# Sheet1.net
KiCad netlist of a schematic drawn in Altium Designer
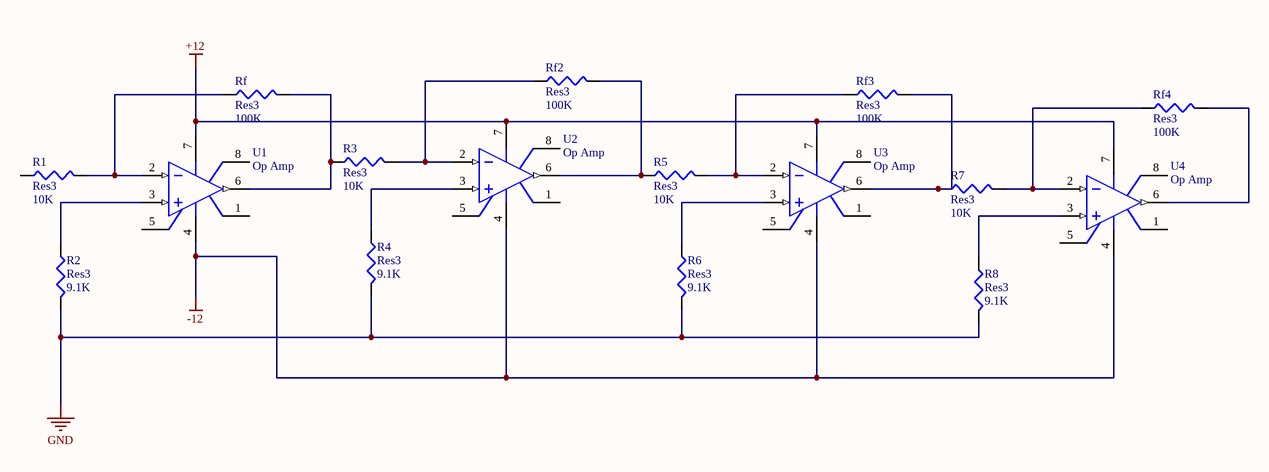
[diagram p0: Sheet1.SchDoc]

(export (version "E")
  (design (tool "Eeschema 10.0.6"))
  (components
    (comp (ref "R1")
      (value "Res3")
      (footprint "J1-0603")
      (description "Resistor")
      (fields (field (name "ALTIUM_VALUE") "10K") (field (name "PUBLISHER") "Altium Limited"))
      (libsource (lib "Miscellaneous Devices") (part "Res3"))
    )
    (comp (ref "R2")
      (value "Res3")
      (footprint "J1-0603")
      (description "Resistor")
      (fields (field (name "ALTIUM_VALUE") "9.1K") (field (name "PUBLISHER") "Altium Limited"))
      (libsource (lib "Miscellaneous Devices") (part "Res3"))
    )
    (comp (ref "R3")
      (value "Res3")
      (footprint "J1-0603")
      (description "Resistor")
      (fields (field (name "ALTIUM_VALUE") "10K") (field (name "PUBLISHER") "Altium Limited"))
      (libsource (lib "Miscellaneous Devices") (part "Res3"))
    )
    (comp (ref "R4")
      (value "Res3")
      (footprint "J1-0603")
      (description "Resistor")
      (fields (field (name "ALTIUM_VALUE") "9.1K") (field (name "PUBLISHER") "Altium Limited"))
      (libsource (lib "Miscellaneous Devices") (part "Res3"))
    )
    (comp (ref "R5")
      (value "Res3")
      (footprint "J1-0603")
      (description "Resistor")
      (fields (field (name "ALTIUM_VALUE") "10K") (field (name "PUBLISHER") "Altium Limited"))
      (libsource (lib "Miscellaneous Devices") (part "Res3"))
    )
    (comp (ref "R6")
      (value "Res3")
      (footprint "J1-0603")
      (description "Resistor")
      (fields (field (name "ALTIUM_VALUE") "9.1K") (field (name "PUBLISHER") "Altium Limited"))
      (libsource (lib "Miscellaneous Devices") (part "Res3"))
    )
    (comp (ref "R7")
      (value "Res3")
      (footprint "J1-0603")
      (description "Resistor")
      (fields (field (name "ALTIUM_VALUE") "10K") (field (name "PUBLISHER") "Altium Limited"))
      (libsource (lib "Miscellaneous Devices") (part "Res3"))
    )
    (comp (ref "R8")
      (value "Res3")
      (footprint "J1-0603")
      (description "Resistor")
      (fields (field (name "ALTIUM_VALUE") "9.1K") (field (name "PUBLISHER") "Altium Limited"))
      (libsource (lib "Miscellaneous Devices") (part "Res3"))
    )
    (comp (ref "Rf")
      (value "Res3")
      (footprint "J1-0603")
      (description "Resistor")
      (fields (field (name "ALTIUM_VALUE") "100K") (field (name "PUBLISHER") "Altium Limited"))
      (libsource (lib "Miscellaneous Devices") (part "Res3"))
    )
    (comp (ref "Rf2")
      (value "Res3")
      (footprint "J1-0603")
      (description "Resistor")
      (fields (field (name "ALTIUM_VALUE") "100K") (field (name "PUBLISHER") "Altium Limited"))
      (libsource (lib "Miscellaneous Devices") (part "Res3"))
    )
    (comp (ref "Rf3")
      (value "Res3")
      (footprint "J1-0603")
      (description "Resistor")
      (fields (field (name "ALTIUM_VALUE") "100K") (field (name "PUBLISHER") "Altium Limited"))
      (libsource (lib "Miscellaneous Devices") (part "Res3"))
    )
    (comp (ref "Rf4")
      (value "Res3")
      (footprint "J1-0603")
      (description "Resistor")
      (fields (field (name "ALTIUM_VALUE") "100K") (field (name "PUBLISHER") "Altium Limited"))
      (libsource (lib "Miscellaneous Devices") (part "Res3"))
    )
    (comp (ref "U1")
      (value "Op Amp")
      (footprint "Miscellaneous Devices:DIP-8")
      (description "FET Operational Amplifier")
      (fields (field (name "PUBLISHER") "Altium Limited"))
      (libsource (lib "Miscellaneous Devices") (part "Op Amp"))
    )
    (comp (ref "U2")
      (value "Op Amp")
      (footprint "Miscellaneous Devices:DIP-8")
      (description "FET Operational Amplifier")
      (fields (field (name "PUBLISHER") "Altium Limited"))
      (libsource (lib "Miscellaneous Devices") (part "Op Amp"))
    )
    (comp (ref "U3")
      (value "Op Amp")
      (footprint "Miscellaneous Devices:DIP-8")
      (description "FET Operational Amplifier")
      (fields (field (name "PUBLISHER") "Altium Limited"))
      (libsource (lib "Miscellaneous Devices") (part "Op Amp"))
    )
    (comp (ref "U4")
      (value "Op Amp")
      (footprint "Miscellaneous Devices:DIP-8")
      (description "FET Operational Amplifier")
      (fields (field (name "PUBLISHER") "Altium Limited"))
      (libsource (lib "Miscellaneous Devices") (part "Op Amp"))
    )
  )
  (nets
    (net (code "1") (name "+12") (class "Default")
      (node (ref "U1") (pin "7") (pinfunction "V+_7") (pintype "power_in"))
      (node (ref "U2") (pin "7") (pinfunction "V+_7") (pintype "power_in"))
      (node (ref "U3") (pin "7") (pinfunction "V+_7") (pintype "power_in"))
      (node (ref "U4") (pin "7") (pinfunction "V+_7") (pintype "power_in"))
    )
    (net (code "2") (name "-12") (class "Default")
      (node (ref "U1") (pin "4") (pinfunction "V-_4") (pintype "power_in"))
      (node (ref "U2") (pin "4") (pinfunction "V-_4") (pintype "power_in"))
      (node (ref "U3") (pin "4") (pinfunction "V-_4") (pintype "power_in"))
      (node (ref "U4") (pin "4") (pinfunction "V-_4") (pintype "power_in"))
    )
    (net (code "3") (name "GND") (class "Default")
      (node (ref "R2") (pin "2") (pinfunction "2_2") (pintype "passive"))
      (node (ref "R4") (pin "2") (pinfunction "2_2") (pintype "passive"))
      (node (ref "R6") (pin "2") (pinfunction "2_2") (pintype "passive"))
      (node (ref "R8") (pin "2") (pinfunction "2_2") (pintype "passive"))
    )
    (net (code "4") (name "Net-(U1-IN+)") (class "Default")
      (node (ref "R2") (pin "1") (pinfunction "1_1") (pintype "passive"))
      (node (ref "U1") (pin "3") (pinfunction "IN+_3") (pintype "input"))
    )
    (net (code "5") (name "Net-(U1-IN-)") (class "Default")
      (node (ref "R1") (pin "2") (pinfunction "2_2") (pintype "passive"))
      (node (ref "Rf") (pin "1") (pinfunction "1_1") (pintype "passive"))
      (node (ref "U1") (pin "2") (pinfunction "IN-_2") (pintype "input"))
    )
    (net (code "6") (name "Net-(U1-OUT)") (class "Default")
      (node (ref "R3") (pin "1") (pinfunction "1_1") (pintype "passive"))
      (node (ref "Rf") (pin "2") (pinfunction "2_2") (pintype "passive"))
      (node (ref "U1") (pin "6") (pinfunction "OUT_6") (pintype "output"))
    )
    (net (code "7") (name "Net-(U2-IN+)") (class "Default")
      (node (ref "R4") (pin "1") (pinfunction "1_1") (pintype "passive"))
      (node (ref "U2") (pin "3") (pinfunction "IN+_3") (pintype "input"))
    )
    (net (code "8") (name "Net-(U2-IN-)") (class "Default")
      (node (ref "R3") (pin "2") (pinfunction "2_2") (pintype "passive"))
      (node (ref "Rf2") (pin "1") (pinfunction "1_1") (pintype "passive"))
      (node (ref "U2") (pin "2") (pinfunction "IN-_2") (pintype "input"))
    )
    (net (code "9") (name "Net-(U2-OUT)") (class "Default")
      (node (ref "R5") (pin "1") (pinfunction "1_1") (pintype "passive"))
      (node (ref "Rf2") (pin "2") (pinfunction "2_2") (pintype "passive"))
      (node (ref "U2") (pin "6") (pinfunction "OUT_6") (pintype "output"))
    )
    (net (code "10") (name "Net-(U3-IN+)") (class "Default")
      (node (ref "R6") (pin "1") (pinfunction "1_1") (pintype "passive"))
      (node (ref "U3") (pin "3") (pinfunction "IN+_3") (pintype "input"))
    )
    (net (code "11") (name "Net-(U3-IN-)") (class "Default")
      (node (ref "R5") (pin "2") (pinfunction "2_2") (pintype "passive"))
      (node (ref "Rf3") (pin "1") (pinfunction "1_1") (pintype "passive"))
      (node (ref "U3") (pin "2") (pinfunction "IN-_2") (pintype "input"))
    )
    (net (code "12") (name "Net-(U3-OUT)") (class "Default")
      (node (ref "R7") (pin "1") (pinfunction "1_1") (pintype "passive"))
      (node (ref "Rf3") (pin "2") (pinfunction "2_2") (pintype "passive"))
      (node (ref "U3") (pin "6") (pinfunction "OUT_6") (pintype "output"))
    )
    (net (code "13") (name "Net-(U4-IN+)") (class "Default")
      (node (ref "R8") (pin "1") (pinfunction "1_1") (pintype "passive"))
      (node (ref "U4") (pin "3") (pinfunction "IN+_3") (pintype "input"))
    )
    (net (code "14") (name "Net-(U4-IN-)") (class "Default")
      (node (ref "R7") (pin "2") (pinfunction "2_2") (pintype "passive"))
      (node (ref "Rf4") (pin "1") (pinfunction "1_1") (pintype "passive"))
      (node (ref "U4") (pin "2") (pinfunction "IN-_2") (pintype "input"))
    )
    (net (code "15") (name "Net-(U4-OUT)") (class "Default")
      (node (ref "Rf4") (pin "2") (pinfunction "2_2") (pintype "passive"))
      (node (ref "U4") (pin "6") (pinfunction "OUT_6") (pintype "output"))
    )
    (net (code "16") (name "unconnected-(R1-Pad1)") (class "Default")
      (node (ref "R1") (pin "1") (pinfunction "1_1") (pintype "passive"))
    )
    (net (code "17") (name "unconnected-(U1-OS_NUL-Pad1)") (class "Default")
      (node (ref "U1") (pin "1") (pinfunction "OS_NUL_1") (pintype "passive"))
    )
    (net (code "18") (name "unconnected-(U1-OS_NUL-Pad5)") (class "Default")
      (node (ref "U1") (pin "5") (pinfunction "OS_NUL_5") (pintype "passive"))
    )
    (net (code "19") (name "unconnected-(U1-TAB-Pad8)") (class "Default")
      (node (ref "U1") (pin "8") (pinfunction "TAB_8") (pintype "passive"))
    )
    (net (code "20") (name "unconnected-(U2-OS_NUL-Pad1)") (class "Default")
      (node (ref "U2") (pin "1") (pinfunction "OS_NUL_1") (pintype "passive"))
    )
    (net (code "21") (name "unconnected-(U2-OS_NUL-Pad5)") (class "Default")
      (node (ref "U2") (pin "5") (pinfunction "OS_NUL_5") (pintype "passive"))
    )
    (net (code "22") (name "unconnected-(U2-TAB-Pad8)") (class "Default")
      (node (ref "U2") (pin "8") (pinfunction "TAB_8") (pintype "passive"))
    )
    (net (code "23") (name "unconnected-(U3-OS_NUL-Pad1)") (class "Default")
      (node (ref "U3") (pin "1") (pinfunction "OS_NUL_1") (pintype "passive"))
    )
    (net (code "24") (name "unconnected-(U3-OS_NUL-Pad5)") (class "Default")
      (node (ref "U3") (pin "5") (pinfunction "OS_NUL_5") (pintype "passive"))
    )
    (net (code "25") (name "unconnected-(U3-TAB-Pad8)") (class "Default")
      (node (ref "U3") (pin "8") (pinfunction "TAB_8") (pintype "passive"))
    )
    (net (code "26") (name "unconnected-(U4-OS_NUL-Pad1)") (class "Default")
      (node (ref "U4") (pin "1") (pinfunction "OS_NUL_1") (pintype "passive"))
    )
    (net (code "27") (name "unconnected-(U4-OS_NUL-Pad5)") (class "Default")
      (node (ref "U4") (pin "5") (pinfunction "OS_NUL_5") (pintype "passive"))
    )
    (net (code "28") (name "unconnected-(U4-TAB-Pad8)") (class "Default")
      (node (ref "U4") (pin "8") (pinfunction "TAB_8") (pintype "passive"))
    )
  )
)
